# VCXO_25M_DDMTD.net
KiCad netlist of a schematic drawn in Altium Designer
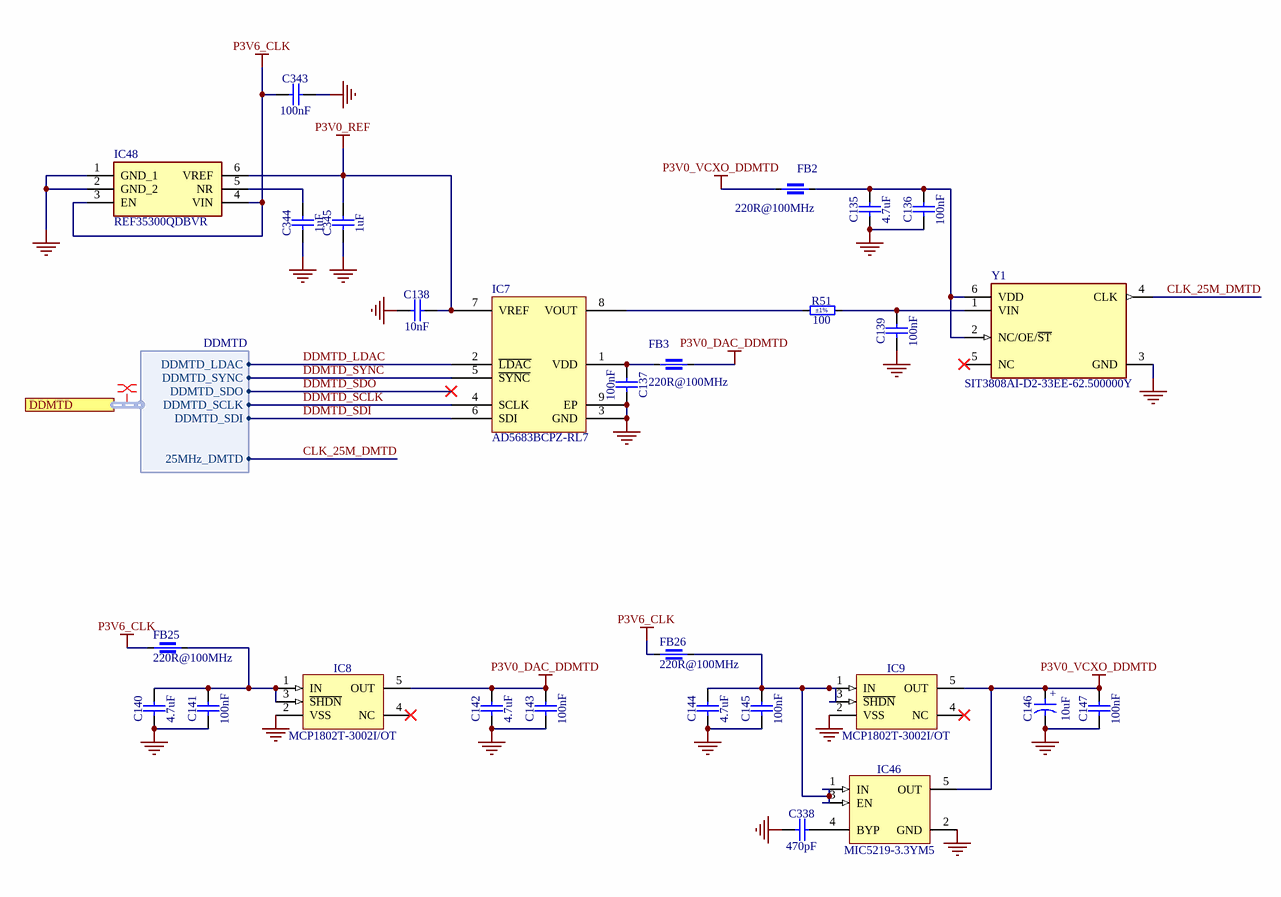
[diagram p0: VCXO_25M_DDMTD.SchDoc]

(export (version "E")
  (design (tool "Eeschema 10.0.6"))
  (components
    (comp (ref "C135")
      (value "4.7uF")
      (footprint "CAPC1005X55N")
      (description "Non-polarised capacitor")
      (fields
        (field (name "PART NUMBER") "CC0402_4.7UF_6.3V_20%_X5R")
        (field (name "VOLTAGE") "6.3V")
        (field (name "AUTHOR") "CERN DEM JLC")
      )
      (libsource (lib "Capacitors") (part "Capacitor - non polarized"))
    )
    (comp (ref "C136")
      (value "100nF")
      (footprint "CAPC0603X33N")
      (description "Non-polarised capacitor")
      (fields
        (field (name "PART NUMBER") "CC0201_100NF_6.3V_10%_X5R")
        (field (name "VOLTAGE") "6.3V")
        (field (name "AUTHOR") "CERN DEM JLC")
      )
      (libsource (lib "Capacitors") (part "Capacitor - non polarized"))
    )
    (comp (ref "C137")
      (value "100nF")
      (footprint "CAPC0603X33N")
      (description "Non-polarised capacitor")
      (fields
        (field (name "PART NUMBER") "CC0201_100NF_6.3V_10%_X5R")
        (field (name "VOLTAGE") "6.3V")
        (field (name "AUTHOR") "CERN DEM JLC")
      )
      (libsource (lib "Capacitors") (part "Capacitor - non polarized"))
    )
    (comp (ref "C138")
      (value "10nF")
      (footprint "CAPC1005X55N")
      (description "Non-polarised capacitor")
      (fields
        (field (name "PART NUMBER") "CC0402_10NF_16V_10%_X7R")
        (field (name "VOLTAGE") "16V")
        (field (name "AUTHOR") "CERN DEM JLC")
      )
      (libsource (lib "Capacitors") (part "Capacitor - non polarized"))
    )
    (comp (ref "C139")
      (value "100nF")
      (footprint "CAPC2012X88N")
      (description "Non-polarised capacitor")
      (fields
        (field (name "PART NUMBER") "CC0805_100NF_50V_1%_NP0")
        (field (name "VOLTAGE") "50V")
        (field (name "AUTHOR") "CERN DEM HF")
      )
      (libsource (lib "Capacitors") (part "Capacitor - non polarized"))
    )
    (comp (ref "C140")
      (value "4.7uF")
      (footprint "CAPC1005X55N")
      (description "Non-polarised capacitor")
      (fields
        (field (name "PART NUMBER") "CC0402_4.7UF_6.3V_20%_X5R")
        (field (name "VOLTAGE") "6.3V")
        (field (name "AUTHOR") "CERN DEM JLC")
      )
      (libsource (lib "Capacitors") (part "Capacitor - non polarized"))
    )
    (comp (ref "C141")
      (value "100nF")
      (footprint "CAPC0603X33N")
      (description "Non-polarised capacitor")
      (fields
        (field (name "PART NUMBER") "CC0201_100NF_6.3V_10%_X5R")
        (field (name "VOLTAGE") "6.3V")
        (field (name "AUTHOR") "CERN DEM JLC")
      )
      (libsource (lib "Capacitors") (part "Capacitor - non polarized"))
    )
    (comp (ref "C142")
      (value "4.7uF")
      (footprint "CAPC1005X55N")
      (description "Non-polarised capacitor")
      (fields
        (field (name "PART NUMBER") "CC0402_4.7UF_6.3V_20%_X5R")
        (field (name "VOLTAGE") "6.3V")
        (field (name "AUTHOR") "CERN DEM JLC")
      )
      (libsource (lib "Capacitors") (part "Capacitor - non polarized"))
    )
    (comp (ref "C143")
      (value "100nF")
      (footprint "CAPC0603X33N")
      (description "Non-polarised capacitor")
      (fields
        (field (name "PART NUMBER") "CC0201_100NF_6.3V_10%_X5R")
        (field (name "VOLTAGE") "6.3V")
        (field (name "AUTHOR") "CERN DEM JLC")
      )
      (libsource (lib "Capacitors") (part "Capacitor - non polarized"))
    )
    (comp (ref "C144")
      (value "4.7uF")
      (footprint "CAPC1005X55N")
      (description "Non-polarised capacitor")
      (fields
        (field (name "PART NUMBER") "CC0402_4.7UF_6.3V_20%_X5R")
        (field (name "VOLTAGE") "6.3V")
        (field (name "AUTHOR") "CERN DEM JLC")
      )
      (libsource (lib "Capacitors") (part "Capacitor - non polarized"))
    )
    (comp (ref "C145")
      (value "100nF")
      (footprint "CAPC0603X33N")
      (description "Non-polarised capacitor")
      (fields
        (field (name "PART NUMBER") "CC0201_100NF_6.3V_10%_X5R")
        (field (name "VOLTAGE") "6.3V")
        (field (name "AUTHOR") "CERN DEM JLC")
      )
      (libsource (lib "Capacitors") (part "Capacitor - non polarized"))
    )
    (comp (ref "C146")
      (value "10uF")
      (footprint "CAPMP3216X180N")
      (description "Polarised capacitor")
      (fields
        (field (name "PART NUMBER") "CTE3216-18_10UF_10V_10%_LESR1800")
        (field (name "VOLTAGE") "10V")
        (field (name "AUTHOR") "CERN DEM JLC")
      )
      (libsource (lib "Capacitors") (part "Capacitor - polarized"))
    )
    (comp (ref "C147")
      (value "100nF")
      (footprint "CAPC0603X33N")
      (description "Non-polarised capacitor")
      (fields
        (field (name "PART NUMBER") "CC0201_100NF_6.3V_10%_X5R")
        (field (name "VOLTAGE") "6.3V")
        (field (name "AUTHOR") "CERN DEM JLC")
      )
      (libsource (lib "Capacitors") (part "Capacitor - non polarized"))
    )
    (comp (ref "C338")
      (value "470pF")
      (footprint "CAPC1005X55N")
      (description "Non-polarised capacitor")
      (fields
        (field (name "PART NUMBER") "CC0402_470PF_50V_10%_X7R")
        (field (name "VOLTAGE") "50V")
        (field (name "AUTHOR") "CERN DEM JLC")
      )
      (libsource (lib "Capacitors") (part "Capacitor - non polarized"))
    )
    (comp (ref "C343")
      (value "100nF")
      (footprint "CAPC0603X33N")
      (description "Non-polarised capacitor")
      (fields
        (field (name "PART NUMBER") "CC0201_100NF_6.3V_10%_X5R")
        (field (name "VOLTAGE") "6.3V")
        (field (name "AUTHOR") "CERN DEM JLC")
      )
      (libsource (lib "Capacitors") (part "Capacitor - non polarized"))
    )
    (comp (ref "C344")
      (value "1uF")
      (footprint "CAPC1005X55N")
      (description "Non-polarised capacitor")
      (fields
        (field (name "PART NUMBER") "CC0402_1UF_16V_10%_X5R")
        (field (name "VOLTAGE") "16V")
        (field (name "AUTHOR") "CERN DEM JLC")
      )
      (libsource (lib "Capacitors") (part "Capacitor - non polarized"))
    )
    (comp (ref "C345")
      (value "1uF")
      (footprint "CAPC1005X55N")
      (description "Non-polarised capacitor")
      (fields
        (field (name "PART NUMBER") "CC0402_1UF_16V_10%_X5R")
        (field (name "VOLTAGE") "16V")
        (field (name "AUTHOR") "CERN DEM JLC")
      )
      (libsource (lib "Capacitors") (part "Capacitor - non polarized"))
    )
    (comp (ref "FB2")
      (value "220R@100MHz")
      (footprint "INDC1608X95N")
      (fields
        (field (name "TOLERANCE") "±25%")
        (field (name "PART NUMBER") "IND0603_MURATA_BLM18SG221TN1")
        (field (name "POWER") "2.5A")
        (field (name "AUTHOR") "CERN DEM MR")
      )
      (libsource (lib "") (part "Ferrite Bead_1"))
    )
    (comp (ref "FB3")
      (value "220R@100MHz")
      (footprint "INDC1608X95N")
      (fields
        (field (name "TOLERANCE") "±25%")
        (field (name "PART NUMBER") "IND0603_MURATA_BLM18SG221TN1")
        (field (name "POWER") "2.5A")
        (field (name "AUTHOR") "CERN DEM MR")
      )
      (libsource (lib "") (part "Ferrite Bead_2"))
    )
    (comp (ref "FB25")
      (value "220R@100MHz")
      (footprint "INDC1608X95N")
      (fields
        (field (name "TOLERANCE") "±25%")
        (field (name "PART NUMBER") "IND0603_MURATA_BLM18SG221TN1")
        (field (name "POWER") "2.5A")
        (field (name "AUTHOR") "CERN DEM MR")
      )
      (libsource (lib "Inductors & Transformers") (part "Ferrite Bead"))
    )
    (comp (ref "FB26")
      (value "220R@100MHz")
      (footprint "INDC1608X95N")
      (fields
        (field (name "TOLERANCE") "±25%")
        (field (name "PART NUMBER") "IND0603_MURATA_BLM18SG221TN1")
        (field (name "POWER") "2.5A")
        (field (name "AUTHOR") "CERN DEM MR")
      )
      (libsource (lib "Inductors & Transformers") (part "Ferrite Bead"))
    )
    (comp (ref "IC7")
      (value "AD5683BCPZ-RL7")
      (footprint "SON50P200X60_HS-9N")
      (description "IC DAC 16BIT V-OUT 8LFCSP 16 Bit Digital to Analog Converter 1 8-LFCSP-UD (2x2)")
      (fields (field (name "MANUFACTURER") "Analog Devices"))
      (libsource (lib "TechnoSystem Workspace") (part "AD5683BCPZ-RL7"))
    )
    (comp (ref "IC8")
      (value "MCP1802T-3002I/OT")
      (footprint "SOT95P270X145-5N")
      (description "300mA, High PSRR, Low Quiescent Current LDO")
      (fields (field (name "MANUFACTURER") "MICROCHIP TECHNOLOGY") (field (name "AUTHOR") "CERN DEM JLC"))
      (libsource (lib "ICs And Semiconductors") (part "MCP1802"))
    )
    (comp (ref "IC9")
      (value "MCP1802T-3002I/OT")
      (footprint "SOT95P270X145-5N")
      (description "300mA, High PSRR, Low Quiescent Current LDO")
      (fields (field (name "MANUFACTURER") "MICROCHIP TECHNOLOGY") (field (name "AUTHOR") "CERN DEM JLC"))
      (libsource (lib "ICs And Semiconductors") (part "MCP1802"))
    )
    (comp (ref "IC46")
      (value "MIC5219-3.3YM5")
      (footprint "SOT95P280X145-5N")
      (description "500mA Peak Output LDO Regulator")
      (fields (field (name "MANUFACTURER") "MICROCHIP TECHNOLOGY") (field (name "AUTHOR") "CERN DEM WB"))
      (libsource (lib "ICs And Semiconductors") (part "MIC5219-X.XYM5"))
    )
    (comp (ref "IC48")
      (value "REF35300QDBVR")
      (footprint "SOT95P280X145-6N")
      (description "\"650-NA QUIESCENT CURRENT, 12-PPM\" Series Voltage Reference IC Fixed 3V V ±0.05% 10 mA SOT-23-6")
      (libsource (lib "TechnoSystem Workspace") (part "REF35300QDBVR"))
    )
    (comp (ref "R51")
      (value "100")
      (footprint "RESC1005X40N")
      (description "Resistor - 1%")
      (fields
        (field (name "TOLERANCE") "±1%")
        (field (name "PART NUMBER") "R0402_100R_1%_0.0625W_100PPM")
        (field (name "POWER") "0.0625W")
        (field (name "AUTHOR") "CERN DEM JLC")
      )
      (libsource (lib "Resistors") (part "Resistor - 1%"))
    )
    (comp (ref "Y1")
      (value "SIT3808AI-D2-33EE-62.500000Y")
      (footprint "FP-SiT3808-D-MFG")
      (description "MEMS OSC VCXO 62.500000MHZ LVCMOS")
      (libsource (lib "Altium Content Vault") (part "8bfd618ea29a5813e13cb2a17d27c64"))
    )
  )
  (nets
    (net (code "2") (name "/CLK_25M_DMTD") (class "Default")
      (node (ref "Y1") (pin "4") (pinfunction "CLK_4") (pintype "output"))
    )
    (net (code "3") (name "/DDMTD_LDAC") (class "Default")
      (node (ref "IC7") (pin "2") (pinfunction "~{LDAC}_2") (pintype "passive"))
    )
    (net (code "4") (name "/DDMTD_SCLK") (class "Default")
      (node (ref "IC7") (pin "4") (pinfunction "SCLK_4") (pintype "passive"))
    )
    (net (code "5") (name "/DDMTD_SDI") (class "Default")
      (node (ref "IC7") (pin "6") (pinfunction "SDI_6") (pintype "passive"))
    )
    (net (code "7") (name "/DDMTD_SYNC") (class "Default")
      (node (ref "IC7") (pin "5") (pinfunction "~{SYNC}_5") (pintype "passive"))
    )
    (net (code "9") (name "GND") (class "Default")
      (node (ref "C135") (pin "1") (pinfunction "1_1") (pintype "passive"))
      (node (ref "C136") (pin "1") (pinfunction "1_1") (pintype "passive"))
      (node (ref "C137") (pin "1") (pinfunction "1_1") (pintype "passive"))
      (node (ref "C138") (pin "1") (pinfunction "1_1") (pintype "passive"))
      (node (ref "C139") (pin "1") (pinfunction "1_1") (pintype "passive"))
      (node (ref "C140") (pin "1") (pinfunction "1_1") (pintype "passive"))
      (node (ref "C141") (pin "1") (pinfunction "1_1") (pintype "passive"))
      (node (ref "C142") (pin "1") (pinfunction "1_1") (pintype "passive"))
      (node (ref "C143") (pin "1") (pinfunction "1_1") (pintype "passive"))
      (node (ref "C144") (pin "1") (pinfunction "1_1") (pintype "passive"))
      (node (ref "C145") (pin "1") (pinfunction "1_1") (pintype "passive"))
      (node (ref "C146") (pin "2") (pinfunction "2_2") (pintype "passive"))
      (node (ref "C147") (pin "1") (pinfunction "1_1") (pintype "passive"))
      (node (ref "C338") (pin "1") (pinfunction "1_1") (pintype "passive"))
      (node (ref "C343") (pin "2") (pinfunction "2_2") (pintype "passive"))
      (node (ref "C344") (pin "1") (pinfunction "1_1") (pintype "passive"))
      (node (ref "C345") (pin "1") (pinfunction "1_1") (pintype "passive"))
      (node (ref "IC46") (pin "2") (pinfunction "GND_2") (pintype "power_in"))
      (node (ref "IC48") (pin "1") (pinfunction "GND_1_1") (pintype "passive"))
      (node (ref "IC48") (pin "2") (pinfunction "GND_2_2") (pintype "passive"))
      (node (ref "IC7") (pin "3") (pinfunction "GND_3") (pintype "passive"))
      (node (ref "IC7") (pin "9") (pinfunction "EP_9") (pintype "passive"))
      (node (ref "IC8") (pin "2") (pinfunction "VSS_2") (pintype "power_in"))
      (node (ref "IC9") (pin "2") (pinfunction "VSS_2") (pintype "power_in"))
      (node (ref "Y1") (pin "3") (pinfunction "GND_3") (pintype "power_in"))
    )
    (net (code "10") (name "Net-(IC7-VDD)") (class "Default")
      (node (ref "C137") (pin "2") (pinfunction "2_2") (pintype "passive"))
      (node (ref "FB3") (pin "2") (pinfunction "2_2") (pintype "passive"))
      (node (ref "IC7") (pin "1") (pinfunction "VDD_1") (pintype "passive"))
    )
    (net (code "11") (name "Net-(IC7-VOUT)") (class "Default")
      (node (ref "IC7") (pin "8") (pinfunction "VOUT_8") (pintype "passive"))
      (node (ref "R51") (pin "1") (pinfunction "1_1") (pintype "passive"))
    )
    (net (code "12") (name "Net-(IC8-IN)") (class "Default")
      (node (ref "C140") (pin "2") (pinfunction "2_2") (pintype "passive"))
      (node (ref "C141") (pin "2") (pinfunction "2_2") (pintype "passive"))
      (node (ref "FB25") (pin "1") (pinfunction "1_1") (pintype "passive"))
      (node (ref "IC8") (pin "1") (pinfunction "IN_1") (pintype "input"))
      (node (ref "IC8") (pin "3") (pinfunction "~{SHDN}_3") (pintype "input"))
    )
    (net (code "13") (name "Net-(IC46-BYP)") (class "Default")
      (node (ref "C338") (pin "2") (pinfunction "2_2") (pintype "passive"))
      (node (ref "IC46") (pin "4") (pinfunction "BYP_4") (pintype "passive"))
    )
    (net (code "14") (name "Net-(IC46-EN)") (class "Default")
      (node (ref "C144") (pin "2") (pinfunction "2_2") (pintype "passive"))
      (node (ref "C145") (pin "2") (pinfunction "2_2") (pintype "passive"))
      (node (ref "FB26") (pin "1") (pinfunction "1_1") (pintype "passive"))
      (node (ref "IC46") (pin "1") (pinfunction "IN_1") (pintype "input"))
      (node (ref "IC46") (pin "3") (pinfunction "EN_3") (pintype "input"))
      (node (ref "IC9") (pin "1") (pinfunction "IN_1") (pintype "input"))
      (node (ref "IC9") (pin "3") (pinfunction "~{SHDN}_3") (pintype "input"))
    )
    (net (code "15") (name "Net-(IC48-NR)") (class "Default")
      (node (ref "C344") (pin "2") (pinfunction "2_2") (pintype "passive"))
      (node (ref "IC48") (pin "5") (pinfunction "NR_5") (pintype "passive"))
    )
    (net (code "16") (name "Net-(Y1-NC{slash}OE{slash}~{ST})") (class "Default")
      (node (ref "C135") (pin "2") (pinfunction "2_2") (pintype "passive"))
      (node (ref "C136") (pin "2") (pinfunction "2_2") (pintype "passive"))
      (node (ref "FB2") (pin "2") (pinfunction "2_2") (pintype "passive"))
      (node (ref "Y1") (pin "2") (pinfunction "NC/OE/~{ST}_2") (pintype "input"))
      (node (ref "Y1") (pin "6") (pinfunction "VDD_6") (pintype "power_in"))
    )
    (net (code "17") (name "Net-(Y1-VIN)") (class "Default")
      (node (ref "C139") (pin "2") (pinfunction "2_2") (pintype "passive"))
      (node (ref "R51") (pin "2") (pinfunction "2_2") (pintype "passive"))
      (node (ref "Y1") (pin "1") (pinfunction "VIN_1") (pintype "power_in"))
    )
    (net (code "18") (name "P3V0_DAC_DDMTD") (class "Default")
      (node (ref "C142") (pin "2") (pinfunction "2_2") (pintype "passive"))
      (node (ref "C143") (pin "2") (pinfunction "2_2") (pintype "passive"))
      (node (ref "FB3") (pin "1") (pinfunction "1_1") (pintype "passive"))
      (node (ref "IC8") (pin "5") (pinfunction "OUT_5") (pintype "power_in"))
    )
    (net (code "19") (name "P3V0_REF") (class "Default")
      (node (ref "C138") (pin "2") (pinfunction "2_2") (pintype "passive"))
      (node (ref "C345") (pin "2") (pinfunction "2_2") (pintype "passive"))
      (node (ref "IC48") (pin "6") (pinfunction "VREF_6") (pintype "passive"))
      (node (ref "IC7") (pin "7") (pinfunction "VREF_7") (pintype "passive"))
    )
    (net (code "20") (name "P3V0_VCXO_DDMTD") (class "Default")
      (node (ref "C146") (pin "1") (pinfunction "1_1") (pintype "passive"))
      (node (ref "C147") (pin "2") (pinfunction "2_2") (pintype "passive"))
      (node (ref "FB2") (pin "1") (pinfunction "1_1") (pintype "passive"))
      (node (ref "IC46") (pin "5") (pinfunction "OUT_5") (pintype "power_in"))
      (node (ref "IC9") (pin "5") (pinfunction "OUT_5") (pintype "power_in"))
    )
    (net (code "21") (name "P3V6_CLK") (class "Default")
      (node (ref "C343") (pin "1") (pinfunction "1_1") (pintype "passive"))
      (node (ref "FB25") (pin "2") (pinfunction "2_2") (pintype "passive"))
      (node (ref "FB26") (pin "2") (pinfunction "2_2") (pintype "passive"))
      (node (ref "IC48") (pin "3") (pinfunction "EN_3") (pintype "passive"))
      (node (ref "IC48") (pin "4") (pinfunction "VIN_4") (pintype "passive"))
    )
    (net (code "22") (name "unconnected-(IC8-NC-Pad4)") (class "Default")
      (node (ref "IC8") (pin "4") (pinfunction "NC_4") (pintype "passive+no_connect"))
    )
    (net (code "23") (name "unconnected-(IC9-NC-Pad4)") (class "Default")
      (node (ref "IC9") (pin "4") (pinfunction "NC_4") (pintype "passive+no_connect"))
    )
    (net (code "24") (name "unconnected-(Y1-NC-Pad5)") (class "Default")
      (node (ref "Y1") (pin "5") (pinfunction "NC_5") (pintype "passive+no_connect"))
    )
  )
)
